# LiFePo4_Charger_Single_to_Chain_3_2_SMD_.net
KiCad netlist of a schematic drawn in EAGLE
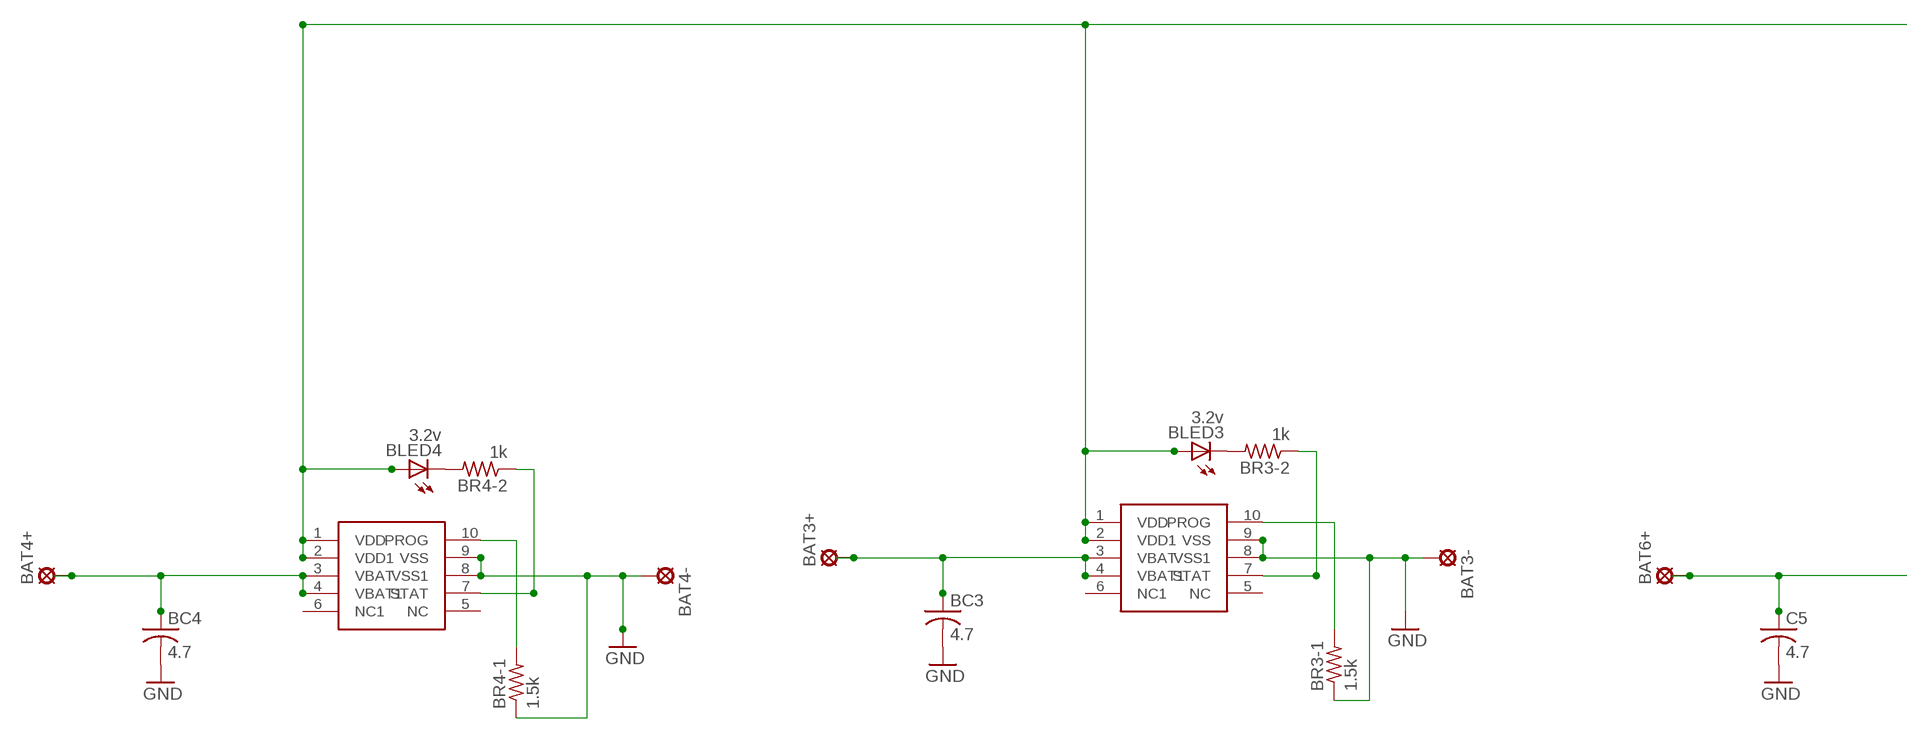
[diagram p0: schematic, sheet 1, part 1 of 2]
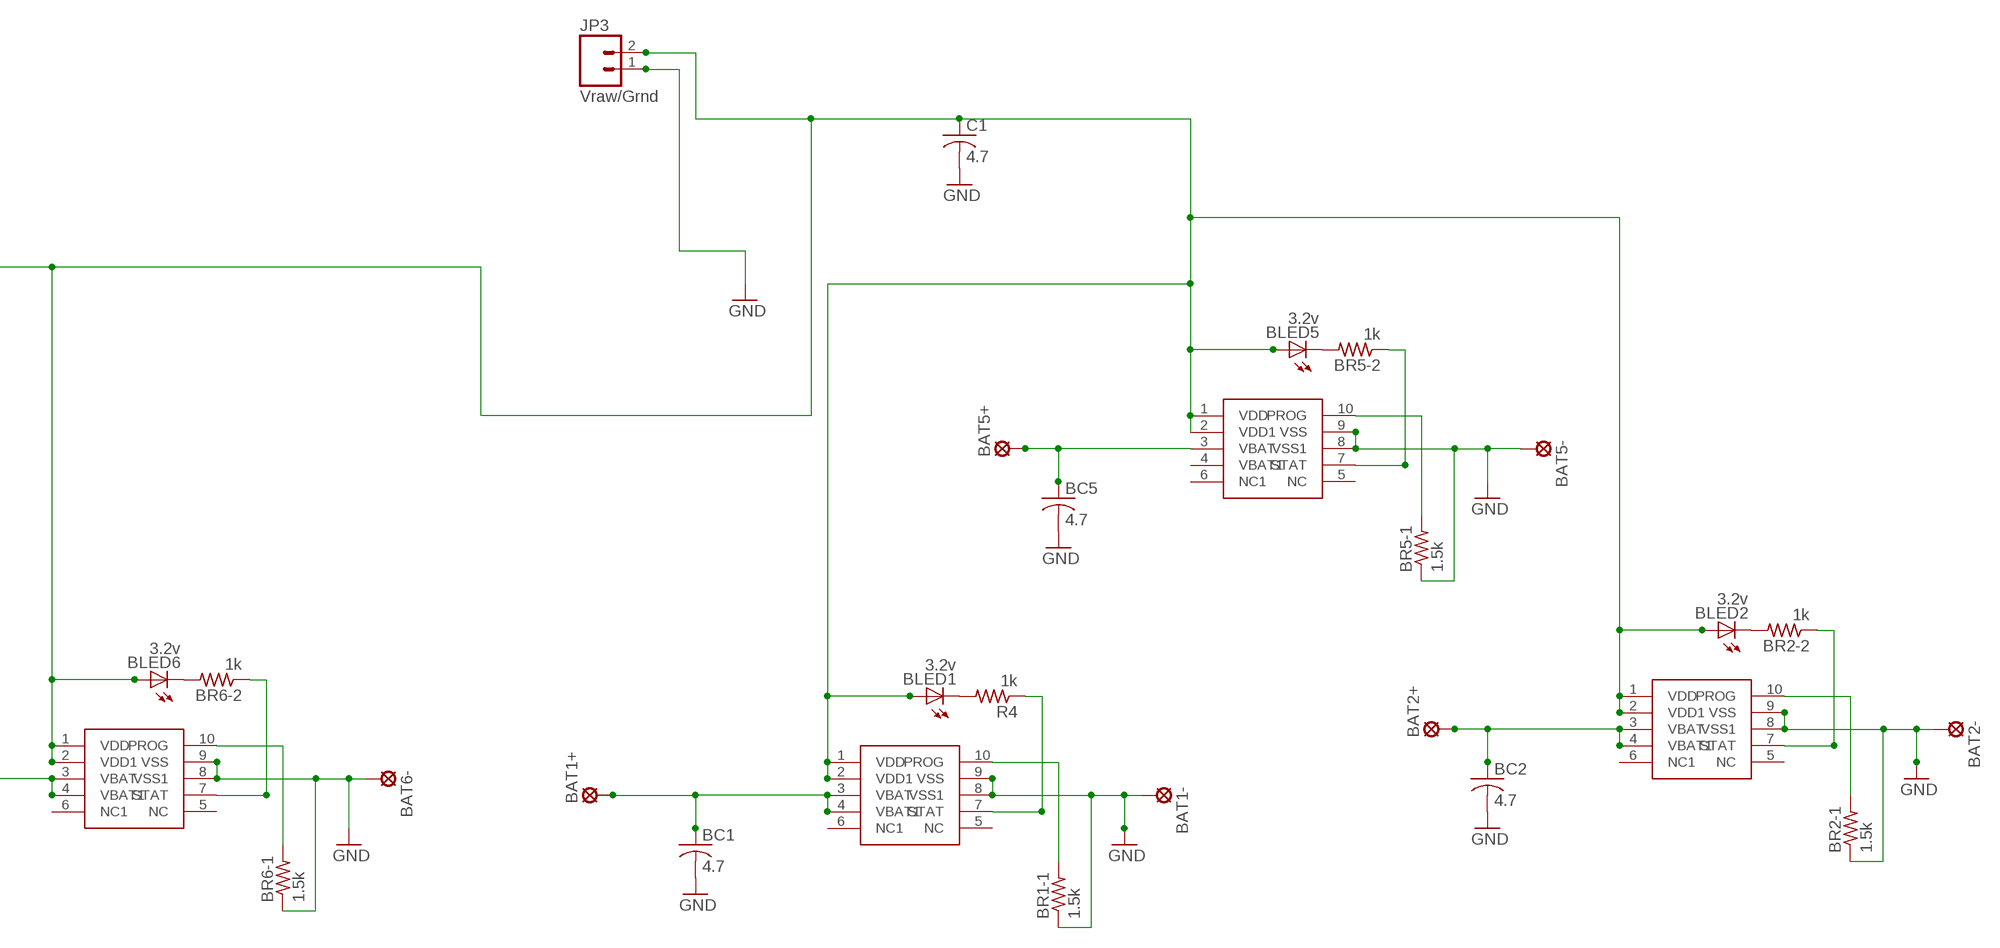
[diagram p1: schematic, sheet 1, part 2 of 2]

(export (version "E")
  (design (tool "Eeschema 10.0.6"))
  (components
    (comp (ref "BAT1+")
      (value "SE14")
      (footprint "eagle-import:SE14")
      (libsource (lib "eagle-import") (part "SE14"))
    )
    (comp (ref "BAT1-")
      (value "SE14")
      (footprint "eagle-import:SE14")
      (libsource (lib "eagle-import") (part "SE14"))
    )
    (comp (ref "BAT2+")
      (value "SE14")
      (footprint "eagle-import:SE14")
      (libsource (lib "eagle-import") (part "SE14"))
    )
    (comp (ref "BAT2-")
      (value "SE14")
      (footprint "eagle-import:SE14")
      (libsource (lib "eagle-import") (part "SE14"))
    )
    (comp (ref "BAT3+")
      (value "SE14")
      (footprint "eagle-import:SE14")
      (libsource (lib "eagle-import") (part "SE14"))
    )
    (comp (ref "BAT3-")
      (value "SE14")
      (footprint "eagle-import:SE14")
      (libsource (lib "eagle-import") (part "SE14"))
    )
    (comp (ref "BAT4+")
      (value "SE14")
      (footprint "eagle-import:SE14")
      (libsource (lib "eagle-import") (part "SE14"))
    )
    (comp (ref "BAT4-")
      (value "SE14")
      (footprint "eagle-import:SE14")
      (libsource (lib "eagle-import") (part "SE14"))
    )
    (comp (ref "BAT5+")
      (value "SE14")
      (footprint "eagle-import:SE14")
      (libsource (lib "eagle-import") (part "SE14"))
    )
    (comp (ref "BAT5-")
      (value "SE14")
      (footprint "eagle-import:SE14")
      (libsource (lib "eagle-import") (part "SE14"))
    )
    (comp (ref "BAT6+")
      (value "SE14")
      (footprint "eagle-import:SE14")
      (libsource (lib "eagle-import") (part "SE14"))
    )
    (comp (ref "BAT6-")
      (value "SE14")
      (footprint "eagle-import:SE14")
      (libsource (lib "eagle-import") (part "SE14"))
    )
    (comp (ref "BC1")
      (value "4.7")
      (footprint "eagle-import:C0805")
      (libsource (lib "eagle-import") (part "C-USC0805"))
    )
    (comp (ref "BC2")
      (value "4.7")
      (footprint "eagle-import:C0805")
      (libsource (lib "eagle-import") (part "C-USC0805"))
    )
    (comp (ref "BC3")
      (value "4.7")
      (footprint "eagle-import:C0805")
      (libsource (lib "eagle-import") (part "C-USC0805"))
    )
    (comp (ref "BC4")
      (value "4.7")
      (footprint "eagle-import:C0805")
      (libsource (lib "eagle-import") (part "C-USC0805"))
    )
    (comp (ref "BC5")
      (value "4.7")
      (footprint "eagle-import:C0805")
      (libsource (lib "eagle-import") (part "C-USC0805"))
    )
    (comp (ref "BLED1")
      (value "3.2v")
      (footprint "eagle-import:SML0603")
      (libsource (lib "eagle-import") (part "LEDSML0603"))
    )
    (comp (ref "BLED2")
      (value "3.2v")
      (footprint "eagle-import:SML0603")
      (libsource (lib "eagle-import") (part "LEDSML0603"))
    )
    (comp (ref "BLED3")
      (value "3.2v")
      (footprint "eagle-import:SML0603")
      (libsource (lib "eagle-import") (part "LEDSML0603"))
    )
    (comp (ref "BLED4")
      (value "3.2v")
      (footprint "eagle-import:SML0603")
      (libsource (lib "eagle-import") (part "LEDSML0603"))
    )
    (comp (ref "BLED5")
      (value "3.2v")
      (footprint "eagle-import:SML0603")
      (libsource (lib "eagle-import") (part "LEDSML0603"))
    )
    (comp (ref "BLED6")
      (value "3.2v")
      (footprint "eagle-import:SML0603")
      (libsource (lib "eagle-import") (part "LEDSML0603"))
    )
    (comp (ref "BR1-1")
      (value "1.5k")
      (footprint "eagle-import:R0805")
      (libsource (lib "eagle-import") (part "R-US_R0805"))
    )
    (comp (ref "BR2-1")
      (value "1.5k")
      (footprint "eagle-import:R0805")
      (libsource (lib "eagle-import") (part "R-US_R0805"))
    )
    (comp (ref "BR2-2")
      (value "1k")
      (footprint "eagle-import:R0805")
      (libsource (lib "eagle-import") (part "R-US_R0805"))
    )
    (comp (ref "BR3-1")
      (value "1.5k")
      (footprint "eagle-import:R0805")
      (libsource (lib "eagle-import") (part "R-US_R0805"))
    )
    (comp (ref "BR3-2")
      (value "1k")
      (footprint "eagle-import:R0805")
      (libsource (lib "eagle-import") (part "R-US_R0805"))
    )
    (comp (ref "BR4-1")
      (value "1.5k")
      (footprint "eagle-import:R0805")
      (libsource (lib "eagle-import") (part "R-US_R0805"))
    )
    (comp (ref "BR4-2")
      (value "1k")
      (footprint "eagle-import:R0805")
      (libsource (lib "eagle-import") (part "R-US_R0805"))
    )
    (comp (ref "BR5-1")
      (value "1.5k")
      (footprint "eagle-import:R0805")
      (libsource (lib "eagle-import") (part "R-US_R0805"))
    )
    (comp (ref "BR5-2")
      (value "1k")
      (footprint "eagle-import:R0805")
      (libsource (lib "eagle-import") (part "R-US_R0805"))
    )
    (comp (ref "BR6-1")
      (value "1.5k")
      (footprint "eagle-import:R0805")
      (libsource (lib "eagle-import") (part "R-US_R0805"))
    )
    (comp (ref "BR6-2")
      (value "1k")
      (footprint "eagle-import:R0805")
      (libsource (lib "eagle-import") (part "R-US_R0805"))
    )
    (comp (ref "C1")
      (value "4.7")
      (footprint "eagle-import:C0805")
      (libsource (lib "eagle-import") (part "C-USC0805"))
    )
    (comp (ref "C5")
      (value "4.7")
      (footprint "eagle-import:C0805")
      (libsource (lib "eagle-import") (part "C-USC0805"))
    )
    (comp (ref "IC2")
      (value "MCP73123/223")
      (footprint "eagle-import:MCP73123_223")
      (libsource (lib "eagle-import") (part "MCP73123/223"))
    )
    (comp (ref "IC4")
      (value "MCP73123/223")
      (footprint "eagle-import:MCP73123_223")
      (libsource (lib "eagle-import") (part "MCP73123/223"))
    )
    (comp (ref "JP3")
      (value "Vraw/Grnd")
      (footprint "eagle-import:1X02")
      (libsource (lib "eagle-import") (part "M02PTH"))
    )
    (comp (ref "R4")
      (value "1k")
      (footprint "eagle-import:R0805")
      (libsource (lib "eagle-import") (part "R-US_R0805"))
    )
    (comp (ref "U$1")
      (value "MCP73123/223")
      (footprint "eagle-import:MCP73123_223")
      (libsource (lib "eagle-import") (part "MCP73123/223"))
    )
    (comp (ref "U$3")
      (value "MCP73123/223")
      (footprint "eagle-import:MCP73123_223")
      (libsource (lib "eagle-import") (part "MCP73123/223"))
    )
    (comp (ref "U$5")
      (value "MCP73123/223")
      (footprint "eagle-import:MCP73123_223")
      (libsource (lib "eagle-import") (part "MCP73123/223"))
    )
    (comp (ref "U$8")
      (value "MCP73123/223")
      (footprint "eagle-import:MCP73123_223")
      (libsource (lib "eagle-import") (part "MCP73123/223"))
    )
  )
  (nets
    (net (code "1") (name "GND") (class "Default")
      (node (ref "BAT1-") (pin "MP") (pinfunction "MP_MP") (pintype "passive"))
      (node (ref "BAT2-") (pin "MP") (pinfunction "MP_MP") (pintype "passive"))
      (node (ref "BAT3-") (pin "MP") (pinfunction "MP_MP") (pintype "passive"))
      (node (ref "BAT4-") (pin "MP") (pinfunction "MP_MP") (pintype "passive"))
      (node (ref "BAT5-") (pin "MP") (pinfunction "MP_MP") (pintype "passive"))
      (node (ref "BAT6-") (pin "MP") (pinfunction "MP_MP") (pintype "passive"))
      (node (ref "BC1") (pin "2") (pinfunction "2_2") (pintype "passive"))
      (node (ref "BC2") (pin "2") (pinfunction "2_2") (pintype "passive"))
      (node (ref "BC3") (pin "2") (pinfunction "2_2") (pintype "passive"))
      (node (ref "BC4") (pin "2") (pinfunction "2_2") (pintype "passive"))
      (node (ref "BC5") (pin "2") (pinfunction "2_2") (pintype "passive"))
      (node (ref "BR1-1") (pin "1") (pinfunction "1_1") (pintype "passive"))
      (node (ref "BR2-1") (pin "1") (pinfunction "1_1") (pintype "passive"))
      (node (ref "BR3-1") (pin "1") (pinfunction "1_1") (pintype "passive"))
      (node (ref "BR4-1") (pin "1") (pinfunction "1_1") (pintype "passive"))
      (node (ref "BR5-1") (pin "1") (pinfunction "1_1") (pintype "passive"))
      (node (ref "BR6-1") (pin "1") (pinfunction "1_1") (pintype "passive"))
      (node (ref "C1") (pin "2") (pinfunction "2_2") (pintype "passive"))
      (node (ref "C5") (pin "2") (pinfunction "2_2") (pintype "passive"))
      (node (ref "IC2") (pin "8") (pinfunction "VSS1_8") (pintype "bidirectional"))
      (node (ref "IC2") (pin "9") (pinfunction "VSS_9") (pintype "bidirectional"))
      (node (ref "IC4") (pin "8") (pinfunction "VSS1_8") (pintype "bidirectional"))
      (node (ref "IC4") (pin "9") (pinfunction "VSS_9") (pintype "bidirectional"))
      (node (ref "JP3") (pin "1") (pinfunction "1_1") (pintype "passive"))
      (node (ref "U$1") (pin "8") (pinfunction "VSS1_8") (pintype "bidirectional"))
      (node (ref "U$1") (pin "9") (pinfunction "VSS_9") (pintype "bidirectional"))
      (node (ref "U$3") (pin "8") (pinfunction "VSS1_8") (pintype "bidirectional"))
      (node (ref "U$3") (pin "9") (pinfunction "VSS_9") (pintype "bidirectional"))
      (node (ref "U$5") (pin "8") (pinfunction "VSS1_8") (pintype "bidirectional"))
      (node (ref "U$5") (pin "9") (pinfunction "VSS_9") (pintype "bidirectional"))
      (node (ref "U$8") (pin "8") (pinfunction "VSS1_8") (pintype "bidirectional"))
      (node (ref "U$8") (pin "9") (pinfunction "VSS_9") (pintype "bidirectional"))
    )
    (net (code "2") (name "Net-(BLED1-PadC)") (class "Default")
      (node (ref "BLED1") (pin "C") (pinfunction "C_C") (pintype "passive"))
      (node (ref "R4") (pin "2") (pinfunction "2_2") (pintype "passive"))
    )
    (net (code "3") (name "Net-(BLED2-PadC)") (class "Default")
      (node (ref "BLED2") (pin "C") (pinfunction "C_C") (pintype "passive"))
      (node (ref "BR2-2") (pin "2") (pinfunction "2_2") (pintype "passive"))
    )
    (net (code "4") (name "Net-(BLED3-PadC)") (class "Default")
      (node (ref "BLED3") (pin "C") (pinfunction "C_C") (pintype "passive"))
      (node (ref "BR3-2") (pin "2") (pinfunction "2_2") (pintype "passive"))
    )
    (net (code "5") (name "Net-(BLED4-PadC)") (class "Default")
      (node (ref "BLED4") (pin "C") (pinfunction "C_C") (pintype "passive"))
      (node (ref "BR4-2") (pin "2") (pinfunction "2_2") (pintype "passive"))
    )
    (net (code "6") (name "Net-(BLED5-PadC)") (class "Default")
      (node (ref "BLED5") (pin "C") (pinfunction "C_C") (pintype "passive"))
      (node (ref "BR5-2") (pin "2") (pinfunction "2_2") (pintype "passive"))
    )
    (net (code "7") (name "Net-(BLED6-PadC)") (class "Default")
      (node (ref "BLED6") (pin "C") (pinfunction "C_C") (pintype "passive"))
      (node (ref "BR6-2") (pin "2") (pinfunction "2_2") (pintype "passive"))
    )
    (net (code "8") (name "Net-(IC2-PROG)") (class "Default")
      (node (ref "BR2-1") (pin "2") (pinfunction "2_2") (pintype "passive"))
      (node (ref "IC2") (pin "10") (pinfunction "PROG_10") (pintype "bidirectional"))
    )
    (net (code "9") (name "Net-(IC2-STAT)") (class "Default")
      (node (ref "BR2-2") (pin "1") (pinfunction "1_1") (pintype "passive"))
      (node (ref "IC2") (pin "7") (pinfunction "STAT_7") (pintype "bidirectional"))
    )
    (net (code "10") (name "Net-(IC2-VBAT)") (class "Default")
      (node (ref "BAT2+") (pin "MP") (pinfunction "MP_MP") (pintype "passive"))
      (node (ref "BC2") (pin "1") (pinfunction "1_1") (pintype "passive"))
      (node (ref "IC2") (pin "3") (pinfunction "VBAT_3") (pintype "bidirectional"))
      (node (ref "IC2") (pin "4") (pinfunction "VBAT1_4") (pintype "bidirectional"))
    )
    (net (code "11") (name "Net-(IC2-VDD)") (class "Default")
      (node (ref "BLED1") (pin "A") (pinfunction "A_A") (pintype "passive"))
      (node (ref "BLED2") (pin "A") (pinfunction "A_A") (pintype "passive"))
      (node (ref "BLED3") (pin "A") (pinfunction "A_A") (pintype "passive"))
      (node (ref "BLED4") (pin "A") (pinfunction "A_A") (pintype "passive"))
      (node (ref "BLED5") (pin "A") (pinfunction "A_A") (pintype "passive"))
      (node (ref "BLED6") (pin "A") (pinfunction "A_A") (pintype "passive"))
      (node (ref "C1") (pin "1") (pinfunction "1_1") (pintype "passive"))
      (node (ref "IC2") (pin "1") (pinfunction "VDD_1") (pintype "bidirectional"))
      (node (ref "IC2") (pin "2") (pinfunction "VDD1_2") (pintype "bidirectional"))
      (node (ref "IC4") (pin "1") (pinfunction "VDD_1") (pintype "bidirectional"))
      (node (ref "IC4") (pin "2") (pinfunction "VDD1_2") (pintype "bidirectional"))
      (node (ref "JP3") (pin "2") (pinfunction "2_2") (pintype "passive"))
      (node (ref "U$1") (pin "1") (pinfunction "VDD_1") (pintype "bidirectional"))
      (node (ref "U$1") (pin "2") (pinfunction "VDD1_2") (pintype "bidirectional"))
      (node (ref "U$3") (pin "1") (pinfunction "VDD_1") (pintype "bidirectional"))
      (node (ref "U$3") (pin "2") (pinfunction "VDD1_2") (pintype "bidirectional"))
      (node (ref "U$5") (pin "1") (pinfunction "VDD_1") (pintype "bidirectional"))
      (node (ref "U$5") (pin "2") (pinfunction "VDD1_2") (pintype "bidirectional"))
      (node (ref "U$8") (pin "1") (pinfunction "VDD_1") (pintype "bidirectional"))
      (node (ref "U$8") (pin "2") (pinfunction "VDD1_2") (pintype "bidirectional"))
    )
    (net (code "12") (name "Net-(IC4-PROG)") (class "Default")
      (node (ref "BR4-1") (pin "2") (pinfunction "2_2") (pintype "passive"))
      (node (ref "IC4") (pin "10") (pinfunction "PROG_10") (pintype "bidirectional"))
    )
    (net (code "13") (name "Net-(IC4-STAT)") (class "Default")
      (node (ref "BR4-2") (pin "1") (pinfunction "1_1") (pintype "passive"))
      (node (ref "IC4") (pin "7") (pinfunction "STAT_7") (pintype "bidirectional"))
    )
    (net (code "14") (name "Net-(IC4-VBAT)") (class "Default")
      (node (ref "BAT4+") (pin "MP") (pinfunction "MP_MP") (pintype "passive"))
      (node (ref "BC4") (pin "1") (pinfunction "1_1") (pintype "passive"))
      (node (ref "IC4") (pin "3") (pinfunction "VBAT_3") (pintype "bidirectional"))
      (node (ref "IC4") (pin "4") (pinfunction "VBAT1_4") (pintype "bidirectional"))
    )
    (net (code "15") (name "Net-(U$1-PROG)") (class "Default")
      (node (ref "BR1-1") (pin "2") (pinfunction "2_2") (pintype "passive"))
      (node (ref "U$1") (pin "10") (pinfunction "PROG_10") (pintype "bidirectional"))
    )
    (net (code "16") (name "Net-(U$1-STAT)") (class "Default")
      (node (ref "R4") (pin "1") (pinfunction "1_1") (pintype "passive"))
      (node (ref "U$1") (pin "7") (pinfunction "STAT_7") (pintype "bidirectional"))
    )
    (net (code "17") (name "Net-(U$1-VBAT)") (class "Default")
      (node (ref "BAT1+") (pin "MP") (pinfunction "MP_MP") (pintype "passive"))
      (node (ref "BC1") (pin "1") (pinfunction "1_1") (pintype "passive"))
      (node (ref "U$1") (pin "3") (pinfunction "VBAT_3") (pintype "bidirectional"))
      (node (ref "U$1") (pin "4") (pinfunction "VBAT1_4") (pintype "bidirectional"))
    )
    (net (code "18") (name "Net-(U$3-PROG)") (class "Default")
      (node (ref "BR6-1") (pin "2") (pinfunction "2_2") (pintype "passive"))
      (node (ref "U$3") (pin "10") (pinfunction "PROG_10") (pintype "bidirectional"))
    )
    (net (code "19") (name "Net-(U$3-STAT)") (class "Default")
      (node (ref "BR6-2") (pin "1") (pinfunction "1_1") (pintype "passive"))
      (node (ref "U$3") (pin "7") (pinfunction "STAT_7") (pintype "bidirectional"))
    )
    (net (code "20") (name "Net-(U$3-VBAT)") (class "Default")
      (node (ref "BAT6+") (pin "MP") (pinfunction "MP_MP") (pintype "passive"))
      (node (ref "C5") (pin "1") (pinfunction "1_1") (pintype "passive"))
      (node (ref "U$3") (pin "3") (pinfunction "VBAT_3") (pintype "bidirectional"))
      (node (ref "U$3") (pin "4") (pinfunction "VBAT1_4") (pintype "bidirectional"))
    )
    (net (code "21") (name "Net-(U$5-PROG)") (class "Default")
      (node (ref "BR3-1") (pin "2") (pinfunction "2_2") (pintype "passive"))
      (node (ref "U$5") (pin "10") (pinfunction "PROG_10") (pintype "bidirectional"))
    )
    (net (code "22") (name "Net-(U$5-STAT)") (class "Default")
      (node (ref "BR3-2") (pin "1") (pinfunction "1_1") (pintype "passive"))
      (node (ref "U$5") (pin "7") (pinfunction "STAT_7") (pintype "bidirectional"))
    )
    (net (code "23") (name "Net-(U$5-VBAT)") (class "Default")
      (node (ref "BAT3+") (pin "MP") (pinfunction "MP_MP") (pintype "passive"))
      (node (ref "BC3") (pin "1") (pinfunction "1_1") (pintype "passive"))
      (node (ref "U$5") (pin "3") (pinfunction "VBAT_3") (pintype "bidirectional"))
      (node (ref "U$5") (pin "4") (pinfunction "VBAT1_4") (pintype "bidirectional"))
    )
    (net (code "24") (name "Net-(U$8-PROG)") (class "Default")
      (node (ref "BR5-1") (pin "2") (pinfunction "2_2") (pintype "passive"))
      (node (ref "U$8") (pin "10") (pinfunction "PROG_10") (pintype "bidirectional"))
    )
    (net (code "25") (name "Net-(U$8-STAT)") (class "Default")
      (node (ref "BR5-2") (pin "1") (pinfunction "1_1") (pintype "passive"))
      (node (ref "U$8") (pin "7") (pinfunction "STAT_7") (pintype "bidirectional"))
    )
    (net (code "26") (name "Net-(U$8-VBAT)") (class "Default")
      (node (ref "BAT5+") (pin "MP") (pinfunction "MP_MP") (pintype "passive"))
      (node (ref "BC5") (pin "1") (pinfunction "1_1") (pintype "passive"))
      (node (ref "U$8") (pin "3") (pinfunction "VBAT_3") (pintype "bidirectional"))
    )
    (net (code "27") (name "unconnected-(IC2-NC-Pad5)") (class "Default")
      (node (ref "IC2") (pin "5") (pinfunction "NC_5") (pintype "bidirectional"))
    )
    (net (code "28") (name "unconnected-(IC2-NC1-Pad6)") (class "Default")
      (node (ref "IC2") (pin "6") (pinfunction "NC1_6") (pintype "bidirectional"))
    )
    (net (code "29") (name "unconnected-(IC4-NC-Pad5)") (class "Default")
      (node (ref "IC4") (pin "5") (pinfunction "NC_5") (pintype "bidirectional"))
    )
    (net (code "30") (name "unconnected-(IC4-NC1-Pad6)") (class "Default")
      (node (ref "IC4") (pin "6") (pinfunction "NC1_6") (pintype "bidirectional"))
    )
    (net (code "31") (name "unconnected-(U$1-NC-Pad5)") (class "Default")
      (node (ref "U$1") (pin "5") (pinfunction "NC_5") (pintype "bidirectional"))
    )
    (net (code "32") (name "unconnected-(U$1-NC1-Pad6)") (class "Default")
      (node (ref "U$1") (pin "6") (pinfunction "NC1_6") (pintype "bidirectional"))
    )
    (net (code "33") (name "unconnected-(U$3-NC-Pad5)") (class "Default")
      (node (ref "U$3") (pin "5") (pinfunction "NC_5") (pintype "bidirectional"))
    )
    (net (code "34") (name "unconnected-(U$3-NC1-Pad6)") (class "Default")
      (node (ref "U$3") (pin "6") (pinfunction "NC1_6") (pintype "bidirectional"))
    )
    (net (code "35") (name "unconnected-(U$5-NC-Pad5)") (class "Default")
      (node (ref "U$5") (pin "5") (pinfunction "NC_5") (pintype "bidirectional"))
    )
    (net (code "36") (name "unconnected-(U$5-NC1-Pad6)") (class "Default")
      (node (ref "U$5") (pin "6") (pinfunction "NC1_6") (pintype "bidirectional"))
    )
    (net (code "37") (name "unconnected-(U$8-NC-Pad5)") (class "Default")
      (node (ref "U$8") (pin "5") (pinfunction "NC_5") (pintype "bidirectional"))
    )
    (net (code "38") (name "unconnected-(U$8-NC1-Pad6)") (class "Default")
      (node (ref "U$8") (pin "6") (pinfunction "NC1_6") (pintype "bidirectional"))
    )
    (net (code "39") (name "unconnected-(U$8-VBAT1-Pad4)") (class "Default")
      (node (ref "U$8") (pin "4") (pinfunction "VBAT1_4") (pintype "bidirectional"))
    )
  )
)
